# TTS.net
KiCad netlist of a schematic drawn in EAGLE
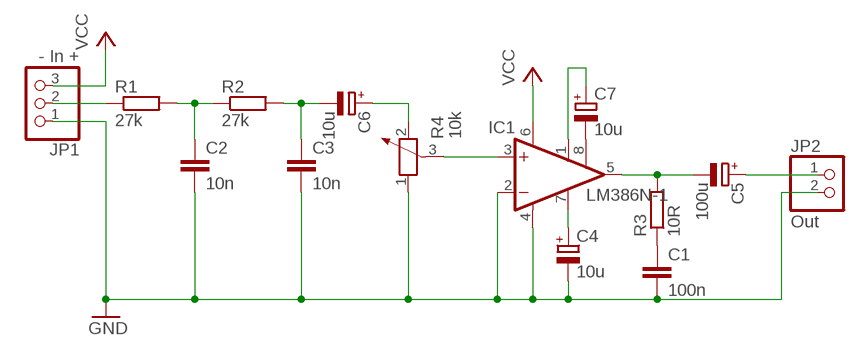
[diagram p0: schematic, sheet 1]

(export (version "E")
  (design (tool "Eeschema 10.0.6"))
  (components
    (comp (ref "C1")
      (value "100n")
      (footprint "eagle-import:C050-024X044")
      (libsource (lib "eagle-import") (part "resistor_C-EU050-024X044"))
    )
    (comp (ref "C2")
      (value "10n")
      (footprint "eagle-import:C050-024X044")
      (libsource (lib "eagle-import") (part "C-EU050-024X044"))
    )
    (comp (ref "C3")
      (value "10n")
      (footprint "eagle-import:C050-024X044")
      (libsource (lib "eagle-import") (part "C-EU050-024X044"))
    )
    (comp (ref "C4")
      (value "10u")
      (footprint "eagle-import:E2,5-5")
      (libsource (lib "eagle-import") (part "CPOL-EUE2.5-5"))
    )
    (comp (ref "C5")
      (value "100u")
      (footprint "eagle-import:E2,5-6")
      (libsource (lib "eagle-import") (part "CPOL-EUE2.5-6"))
    )
    (comp (ref "C6")
      (value "10u")
      (footprint "eagle-import:E2,5-5")
      (libsource (lib "eagle-import") (part "CPOL-EUE2.5-5"))
    )
    (comp (ref "C7")
      (value "10u")
      (footprint "eagle-import:E2,5-5")
      (libsource (lib "eagle-import") (part "CPOL-EUE2.5-5"))
    )
    (comp (ref "IC1")
      (value "LM386N-1")
      (footprint "eagle-import:DIL08")
      (libsource (lib "eagle-import") (part "LM386?-N1"))
    )
    (comp (ref "JP1")
      (value "- In +")
      (footprint "eagle-import:1X03")
      (libsource (lib "eagle-import") (part "PINHD-1X3"))
    )
    (comp (ref "JP2")
      (value "Out")
      (footprint "eagle-import:1X02")
      (libsource (lib "eagle-import") (part "PINHD-1X2"))
    )
    (comp (ref "R1")
      (value "27k")
      (footprint "eagle-import:0207_10")
      (libsource (lib "eagle-import") (part "R-EU_0207/10"))
    )
    (comp (ref "R2")
      (value "27k")
      (footprint "eagle-import:0207_10")
      (libsource (lib "eagle-import") (part "R-EU_0207/10"))
    )
    (comp (ref "R3")
      (value "10R")
      (footprint "eagle-import:0207_10")
      (libsource (lib "eagle-import") (part "R-EU_0207/10"))
    )
    (comp (ref "R4")
      (value "10k")
      (footprint "eagle-import:PT-10S")
      (libsource (lib "eagle-import") (part "POTENTIOMETER_PT-10S"))
    )
  )
  (nets
    (net (code "1") (name "GND") (class "Default")
      (node (ref "C1") (pin "2") (pinfunction "2_2") (pintype "passive"))
      (node (ref "C2") (pin "2") (pinfunction "2_2") (pintype "passive"))
      (node (ref "C3") (pin "2") (pinfunction "2_2") (pintype "passive"))
      (node (ref "C4") (pin "-") (pinfunction "-_-") (pintype "passive"))
      (node (ref "IC1") (pin "2") (pinfunction "-IN_2") (pintype "input"))
      (node (ref "IC1") (pin "4") (pinfunction "GND_4") (pintype "power_in"))
      (node (ref "JP1") (pin "1") (pinfunction "1_1") (pintype "passive"))
      (node (ref "JP2") (pin "2") (pinfunction "2_2") (pintype "passive"))
      (node (ref "R4") (pin "1") (pinfunction "1_1") (pintype "passive"))
    )
    (net (code "2") (name "Net-(C1-Pad1)") (class "Default")
      (node (ref "C1") (pin "1") (pinfunction "1_1") (pintype "passive"))
      (node (ref "R3") (pin "1") (pinfunction "1_1") (pintype "passive"))
    )
    (net (code "3") (name "Net-(C2-Pad1)") (class "Default")
      (node (ref "C2") (pin "1") (pinfunction "1_1") (pintype "passive"))
      (node (ref "R1") (pin "2") (pinfunction "2_2") (pintype "passive"))
      (node (ref "R2") (pin "1") (pinfunction "1_1") (pintype "passive"))
    )
    (net (code "4") (name "Net-(C3-Pad1)") (class "Default")
      (node (ref "C3") (pin "1") (pinfunction "1_1") (pintype "passive"))
      (node (ref "C6") (pin "-") (pinfunction "-_-") (pintype "passive"))
      (node (ref "R2") (pin "2") (pinfunction "2_2") (pintype "passive"))
    )
    (net (code "5") (name "Net-(C5-Pad+)") (class "Default")
      (node (ref "C5") (pin "+") (pinfunction "+_+") (pintype "passive"))
      (node (ref "JP2") (pin "1") (pinfunction "1_1") (pintype "passive"))
    )
    (net (code "6") (name "Net-(C6-Pad+)") (class "Default")
      (node (ref "C6") (pin "+") (pinfunction "+_+") (pintype "passive"))
      (node (ref "R4") (pin "2") (pinfunction "2_2") (pintype "passive"))
    )
    (net (code "7") (name "Net-(C7-Pad+)") (class "Default")
      (node (ref "C7") (pin "+") (pinfunction "+_+") (pintype "passive"))
      (node (ref "IC1") (pin "1") (pinfunction "GAIN_1") (pintype "passive"))
    )
    (net (code "8") (name "Net-(C7-Pad-)") (class "Default")
      (node (ref "C7") (pin "-") (pinfunction "-_-") (pintype "passive"))
      (node (ref "IC1") (pin "8") (pinfunction "GAIN_8") (pintype "passive"))
    )
    (net (code "9") (name "Net-(IC1-+IN)") (class "Default")
      (node (ref "IC1") (pin "3") (pinfunction "+IN_3") (pintype "input"))
      (node (ref "R4") (pin "3") (pinfunction "3_3") (pintype "passive"))
    )
    (net (code "10") (name "Net-(IC1-BYPASS)") (class "Default")
      (node (ref "C4") (pin "+") (pinfunction "+_+") (pintype "passive"))
      (node (ref "IC1") (pin "7") (pinfunction "BYPASS_7") (pintype "passive"))
    )
    (net (code "11") (name "Net-(IC1-OUT)") (class "Default")
      (node (ref "C5") (pin "-") (pinfunction "-_-") (pintype "passive"))
      (node (ref "IC1") (pin "5") (pinfunction "OUT_5") (pintype "output"))
      (node (ref "R3") (pin "2") (pinfunction "2_2") (pintype "passive"))
    )
    (net (code "12") (name "Net-(JP1-Pad2)") (class "Default")
      (node (ref "JP1") (pin "2") (pinfunction "2_2") (pintype "passive"))
      (node (ref "R1") (pin "1") (pinfunction "1_1") (pintype "passive"))
    )
    (net (code "13") (name "VCC") (class "Default")
      (node (ref "IC1") (pin "6") (pinfunction "VS_6") (pintype "power_in"))
      (node (ref "JP1") (pin "3") (pinfunction "3_3") (pintype "passive"))
    )
  )
)
